# PT08pos.net
KiCad netlist of a schematic drawn in EAGLE
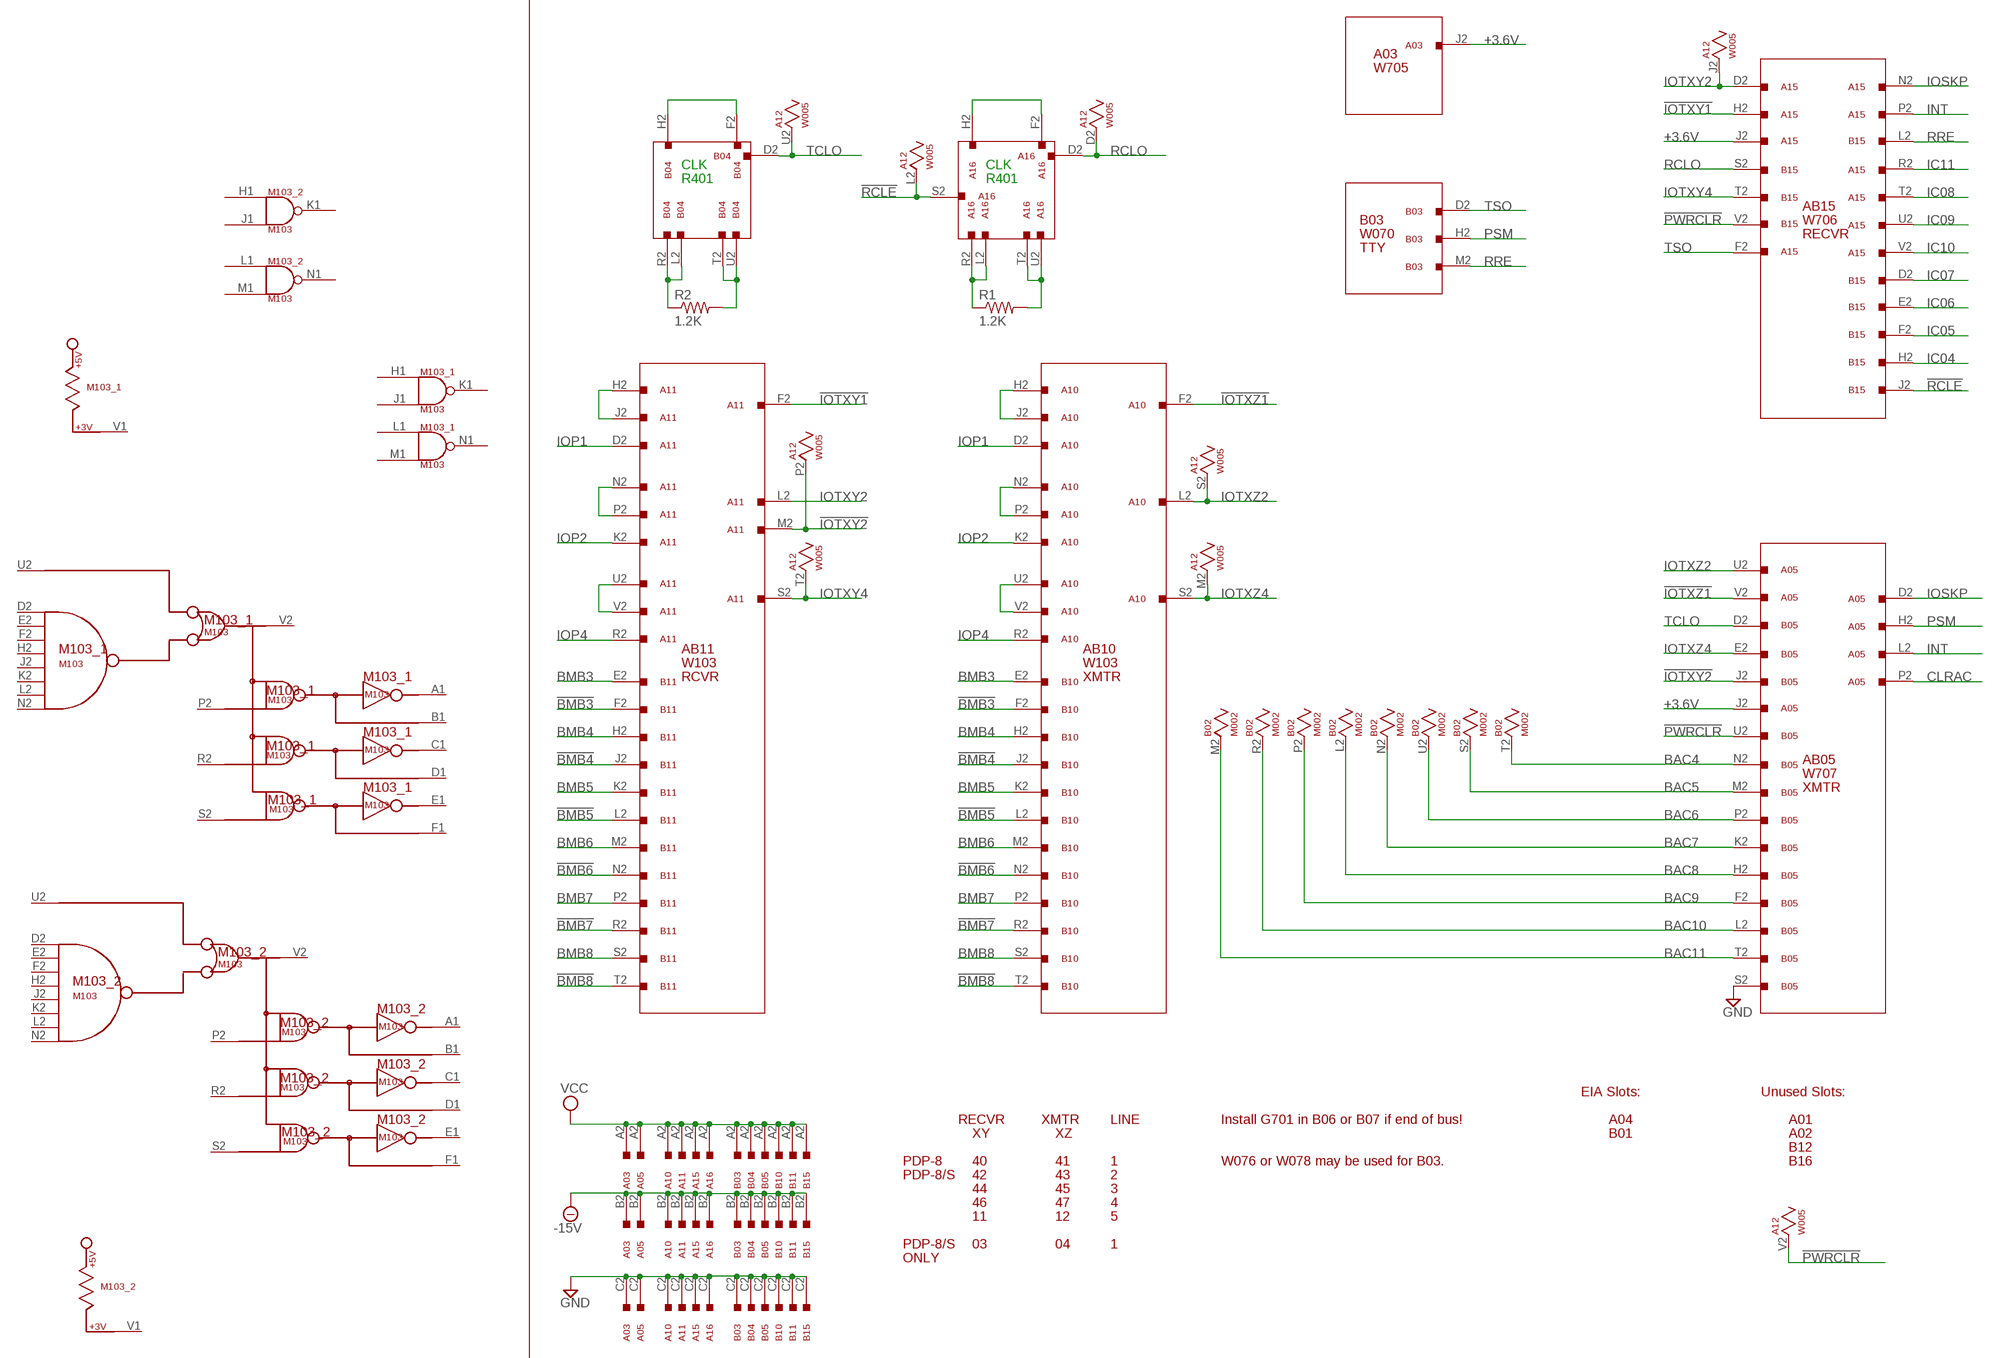
[diagram p0: schematic, sheet 1, part 1 of 2]
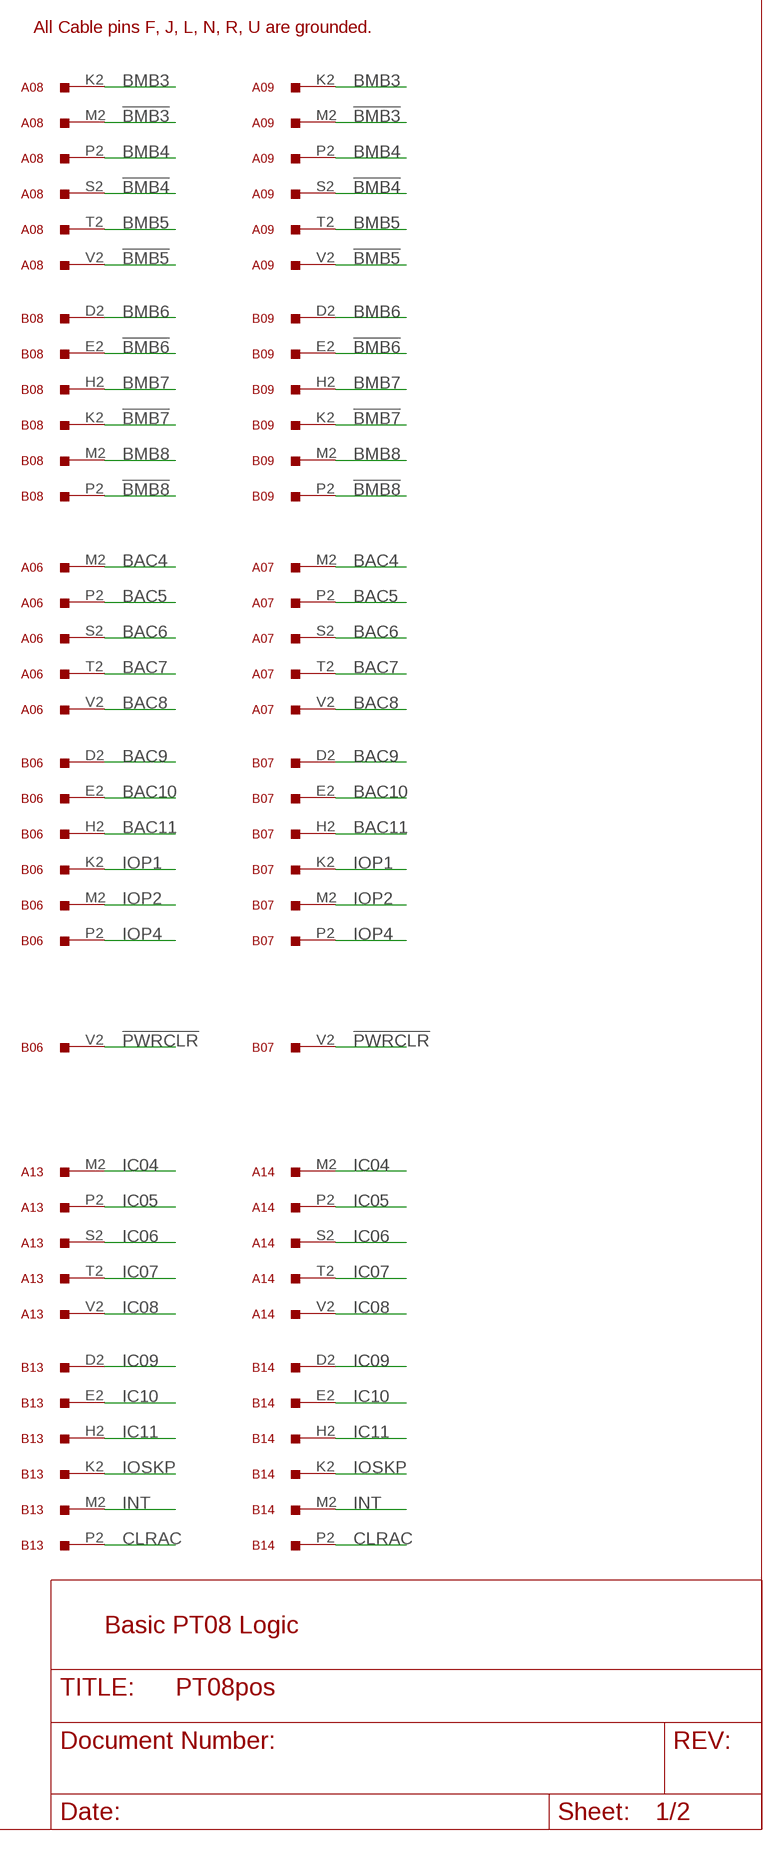
[diagram p1: schematic, sheet 1, part 2 of 2]
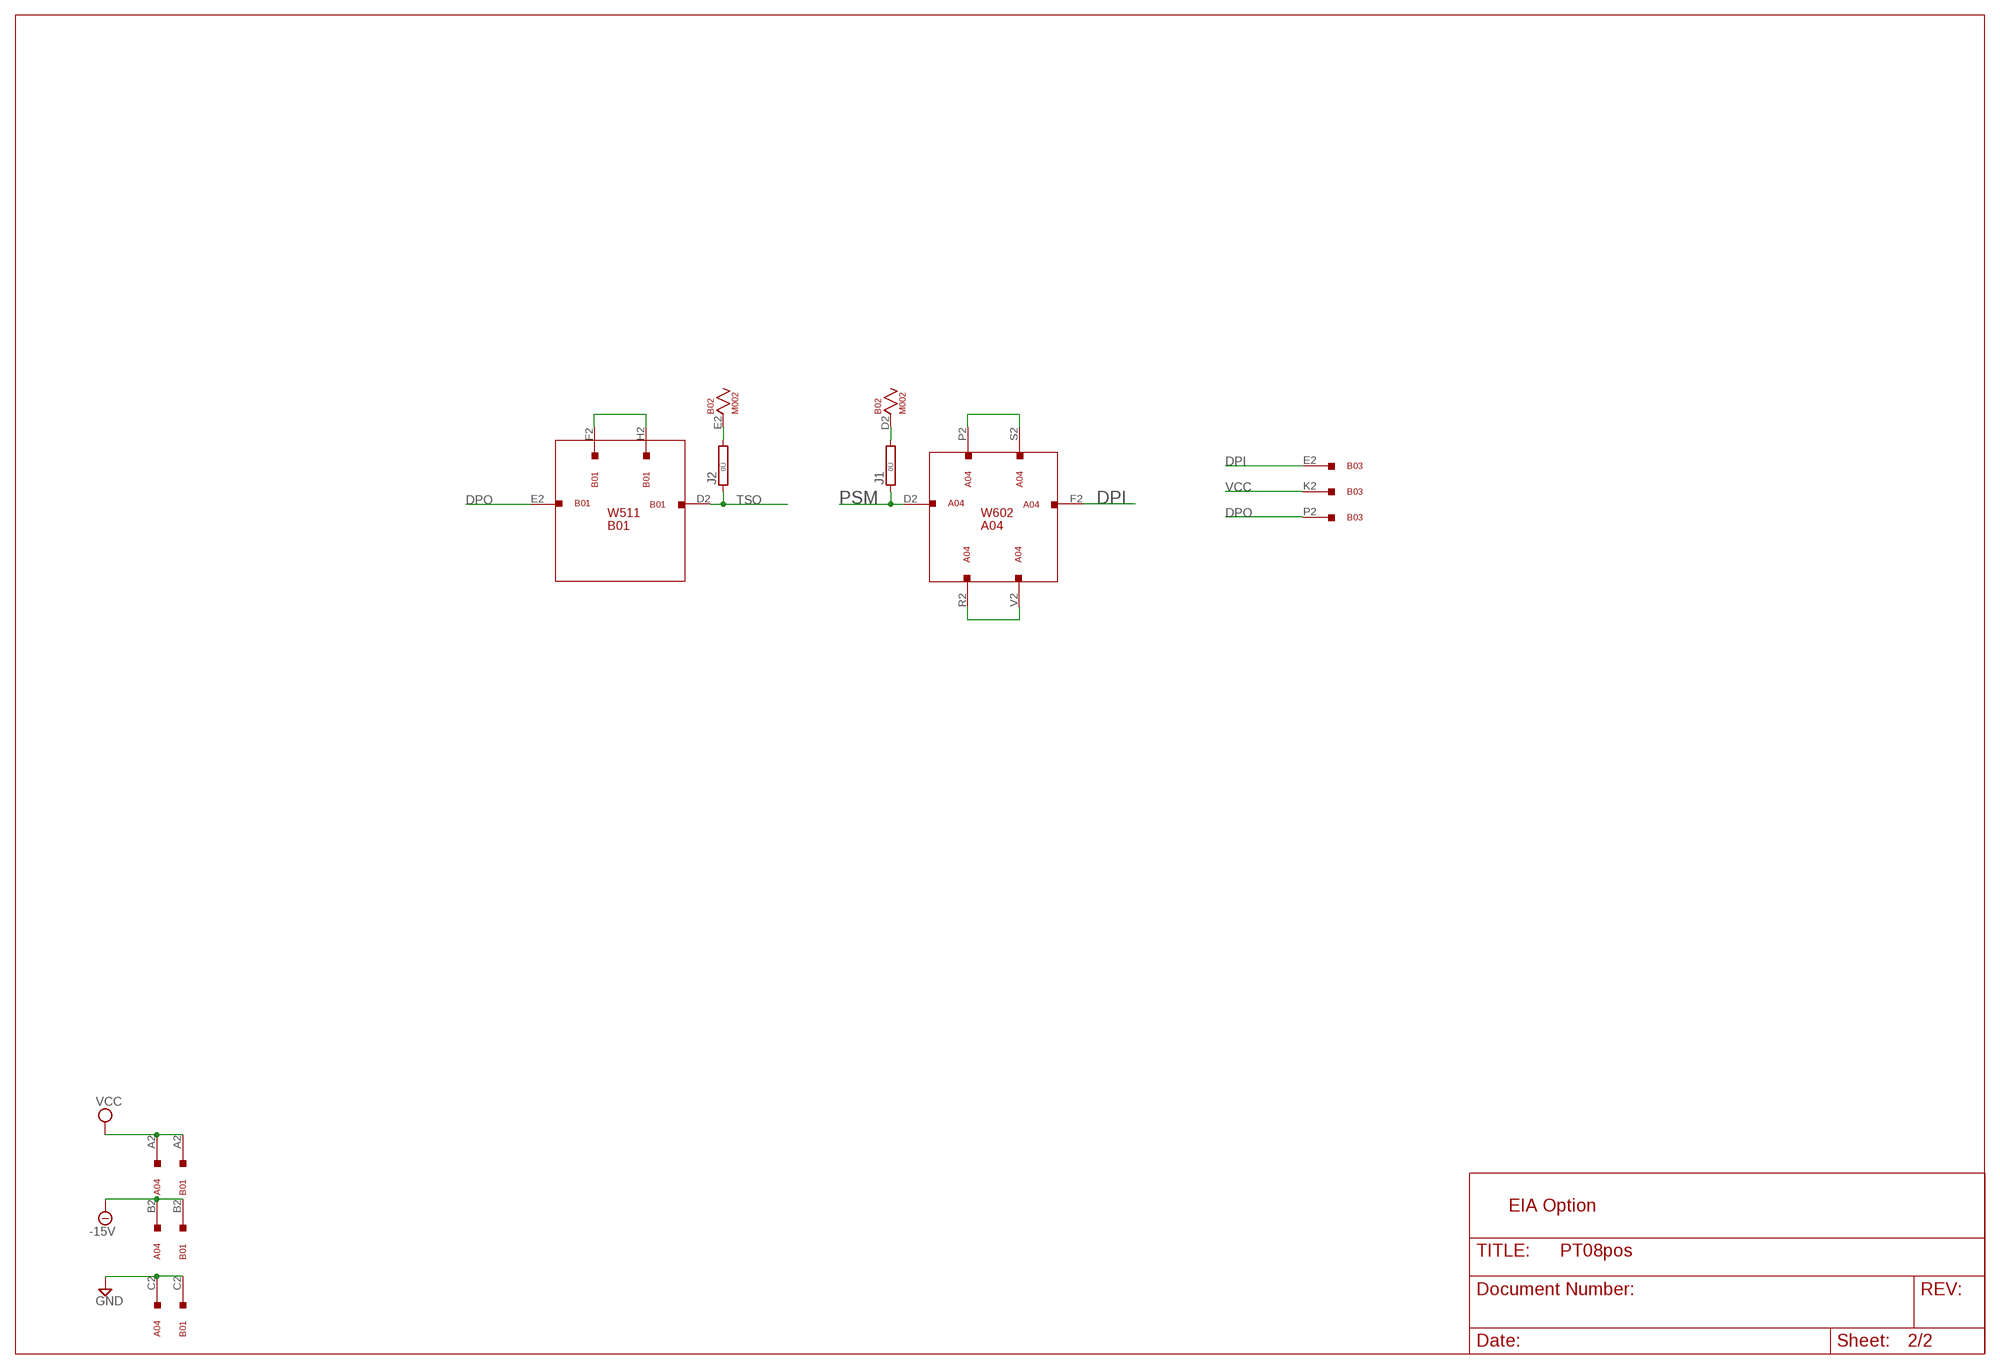
[diagram p2: schematic, sheet 2]

(export (version "E")
  (design (tool "Eeschema 10.0.6"))
  (components
    (comp (ref "A01")
      (value "H807")
      (footprint "eagle-import:H807")
      (libsource (lib "eagle-import") (part "H807"))
    )
    (comp (ref "A02")
      (value "H807")
      (footprint "eagle-import:H807")
      (libsource (lib "eagle-import") (part "H807"))
    )
    (comp (ref "A03")
      (value "W705")
      (footprint "eagle-import:H807")
      (libsource (lib "eagle-import") (part "W023"))
    )
    (comp (ref "A05")
      (value "W707")
      (footprint "eagle-import:H807")
      (libsource (lib "eagle-import") (part "W023"))
    )
    (comp (ref "A06")
      (value "W011")
      (footprint "eagle-import:H807")
      (libsource (lib "eagle-import") (part "W011"))
    )
    (comp (ref "A07")
      (value "W011")
      (footprint "eagle-import:H807")
      (libsource (lib "eagle-import") (part "W011"))
    )
    (comp (ref "A08")
      (value "W011")
      (footprint "eagle-import:H807")
      (libsource (lib "eagle-import") (part "W011"))
    )
    (comp (ref "A09")
      (value "W011")
      (footprint "eagle-import:H807")
      (libsource (lib "eagle-import") (part "W011"))
    )
    (comp (ref "A10")
      (value "W103")
      (footprint "eagle-import:H807")
      (libsource (lib "eagle-import") (part "W023"))
    )
    (comp (ref "A11")
      (value "W103")
      (footprint "eagle-import:H807")
      (libsource (lib "eagle-import") (part "W023"))
    )
    (comp (ref "A12")
      (value "W005")
      (footprint "eagle-import:H807")
      (libsource (lib "eagle-import") (part "W005"))
    )
    (comp (ref "A13")
      (value "W011")
      (footprint "eagle-import:H807")
      (libsource (lib "eagle-import") (part "W011"))
    )
    (comp (ref "A14")
      (value "W011")
      (footprint "eagle-import:H807")
      (libsource (lib "eagle-import") (part "W011"))
    )
    (comp (ref "A15")
      (value "W706")
      (footprint "eagle-import:H807")
      (libsource (lib "eagle-import") (part "W023"))
    )
    (comp (ref "A16")
      (value "R401")
      (footprint "eagle-import:H807")
      (libsource (lib "eagle-import") (part "W023"))
    )
    (comp (ref "B02")
      (value "M002")
      (footprint "eagle-import:H807")
      (libsource (lib "eagle-import") (part "M002"))
    )
    (comp (ref "B03")
      (value "W076")
      (footprint "eagle-import:H807")
      (libsource (lib "eagle-import") (part "W023"))
    )
    (comp (ref "B04")
      (value "R401")
      (footprint "eagle-import:H807")
      (libsource (lib "eagle-import") (part "W023"))
    )
    (comp (ref "B05")
      (value "W707")
      (footprint "eagle-import:H807")
      (libsource (lib "eagle-import") (part "W023"))
    )
    (comp (ref "B06")
      (value "W011")
      (footprint "eagle-import:H807")
      (libsource (lib "eagle-import") (part "W011"))
    )
    (comp (ref "B07")
      (value "W011")
      (footprint "eagle-import:H807")
      (libsource (lib "eagle-import") (part "W011"))
    )
    (comp (ref "B08")
      (value "W011")
      (footprint "eagle-import:H807")
      (libsource (lib "eagle-import") (part "W011"))
    )
    (comp (ref "B09")
      (value "W011")
      (footprint "eagle-import:H807")
      (libsource (lib "eagle-import") (part "W011"))
    )
    (comp (ref "B10")
      (value "W103")
      (footprint "eagle-import:H807")
      (libsource (lib "eagle-import") (part "W023"))
    )
    (comp (ref "B11")
      (value "W103")
      (footprint "eagle-import:H807")
      (libsource (lib "eagle-import") (part "W023"))
    )
    (comp (ref "B12")
      (value "H807")
      (footprint "eagle-import:H807")
      (libsource (lib "eagle-import") (part "H807"))
    )
    (comp (ref "B13")
      (value "W011")
      (footprint "eagle-import:H807")
      (libsource (lib "eagle-import") (part "W011"))
    )
    (comp (ref "B14")
      (value "W011")
      (footprint "eagle-import:H807")
      (libsource (lib "eagle-import") (part "W011"))
    )
    (comp (ref "B15")
      (value "W706")
      (footprint "eagle-import:H807")
      (libsource (lib "eagle-import") (part "W023"))
    )
    (comp (ref "B16")
      (value "H807")
      (footprint "eagle-import:H807")
      (libsource (lib "eagle-import") (part "H807"))
    )
    (comp (ref "M103_1")
      (value "M103")
      (footprint "eagle-import:H807")
      (libsource (lib "eagle-import") (part "M103"))
    )
    (comp (ref "M103_2")
      (value "M103")
      (footprint "eagle-import:H807")
      (libsource (lib "eagle-import") (part "M103"))
    )
    (comp (ref "R1")
      (value "1.2K")
      (footprint "eagle-import:0207_10")
      (libsource (lib "eagle-import") (part "R-US_0207/10"))
    )
    (comp (ref "R2")
      (value "1.2K")
      (footprint "eagle-import:0207_10")
      (libsource (lib "eagle-import") (part "R-US_0207/10"))
    )
    (comp (ref "A04")
      (value "W602")
      (footprint "eagle-import:H807")
      (libsource (lib "eagle-import") (part "W023"))
    )
    (comp (ref "B01")
      (value "W511")
      (footprint "eagle-import:H807")
      (libsource (lib "eagle-import") (part "W023"))
    )
    (comp (ref "J1")
      (value "0R")
      (footprint "eagle-import:0R_10")
      (libsource (lib "eagle-import") (part "0R"))
    )
    (comp (ref "J2")
      (value "0R")
      (footprint "eagle-import:0R_10")
      (libsource (lib "eagle-import") (part "0R"))
    )
  )
  (nets
    (net (code "1") (name "+3.6V") (class "Default")
      (node (ref "A03") (pin "J2") (pinfunction "P$2_J2") (pintype "bidirectional"))
      (node (ref "A05") (pin "J2") (pinfunction "P$2_J2") (pintype "bidirectional"))
      (node (ref "A15") (pin "J2") (pinfunction "P$2_J2") (pintype "bidirectional"))
    )
    (net (code "2") (name "-15V") (class "Default")
      (node (ref "A03") (pin "B2") (pinfunction "P$2_B2") (pintype "bidirectional"))
      (node (ref "A04") (pin "B2") (pinfunction "P$2_B2") (pintype "bidirectional"))
      (node (ref "A05") (pin "B2") (pinfunction "P$2_B2") (pintype "bidirectional"))
      (node (ref "A10") (pin "B2") (pinfunction "P$2_B2") (pintype "bidirectional"))
      (node (ref "A11") (pin "B2") (pinfunction "P$2_B2") (pintype "bidirectional"))
      (node (ref "A15") (pin "B2") (pinfunction "P$2_B2") (pintype "bidirectional"))
      (node (ref "A16") (pin "B2") (pinfunction "P$2_B2") (pintype "bidirectional"))
      (node (ref "B01") (pin "B2") (pinfunction "P$2_B2") (pintype "bidirectional"))
      (node (ref "B03") (pin "B2") (pinfunction "P$2_B2") (pintype "bidirectional"))
      (node (ref "B04") (pin "B2") (pinfunction "P$2_B2") (pintype "bidirectional"))
      (node (ref "B05") (pin "B2") (pinfunction "P$2_B2") (pintype "bidirectional"))
      (node (ref "B10") (pin "B2") (pinfunction "P$2_B2") (pintype "bidirectional"))
      (node (ref "B11") (pin "B2") (pinfunction "P$2_B2") (pintype "bidirectional"))
      (node (ref "B15") (pin "B2") (pinfunction "P$2_B2") (pintype "bidirectional"))
    )
    (net (code "3") (name "BAC4") (class "Default")
      (node (ref "A06") (pin "M2") (pinfunction "P$2_M2") (pintype "bidirectional"))
      (node (ref "A07") (pin "M2") (pinfunction "P$2_M2") (pintype "bidirectional"))
      (node (ref "B02") (pin "T2") (pinfunction "P$1_T2") (pintype "passive"))
      (node (ref "B05") (pin "N2") (pinfunction "P$2_N2") (pintype "bidirectional"))
    )
    (net (code "4") (name "BAC5") (class "Default")
      (node (ref "A06") (pin "P2") (pinfunction "P$2_P2") (pintype "bidirectional"))
      (node (ref "A07") (pin "P2") (pinfunction "P$2_P2") (pintype "bidirectional"))
      (node (ref "B02") (pin "S2") (pinfunction "P$1_S2") (pintype "passive"))
      (node (ref "B05") (pin "M2") (pinfunction "P$2_M2") (pintype "bidirectional"))
    )
    (net (code "5") (name "BAC6") (class "Default")
      (node (ref "A06") (pin "S2") (pinfunction "P$2_S2") (pintype "bidirectional"))
      (node (ref "A07") (pin "S2") (pinfunction "P$2_S2") (pintype "bidirectional"))
      (node (ref "B02") (pin "U2") (pinfunction "P$1_U2") (pintype "passive"))
      (node (ref "B05") (pin "P2") (pinfunction "P$2_P2") (pintype "bidirectional"))
    )
    (net (code "6") (name "BAC7") (class "Default")
      (node (ref "A06") (pin "T2") (pinfunction "P$2_T2") (pintype "bidirectional"))
      (node (ref "A07") (pin "T2") (pinfunction "P$2_T2") (pintype "bidirectional"))
      (node (ref "B02") (pin "N2") (pinfunction "P$1_N2") (pintype "passive"))
      (node (ref "B05") (pin "K2") (pinfunction "P$2_K2") (pintype "bidirectional"))
    )
    (net (code "7") (name "BAC8") (class "Default")
      (node (ref "A06") (pin "V2") (pinfunction "P$2_V2") (pintype "bidirectional"))
      (node (ref "A07") (pin "V2") (pinfunction "P$2_V2") (pintype "bidirectional"))
      (node (ref "B02") (pin "L2") (pinfunction "P$1_L2") (pintype "passive"))
      (node (ref "B05") (pin "H2") (pinfunction "P$2_H2") (pintype "bidirectional"))
    )
    (net (code "8") (name "BAC9") (class "Default")
      (node (ref "B02") (pin "P2") (pinfunction "P$1_P2") (pintype "passive"))
      (node (ref "B05") (pin "F2") (pinfunction "P$2_F2") (pintype "bidirectional"))
      (node (ref "B06") (pin "D2") (pinfunction "P$2_D2") (pintype "bidirectional"))
      (node (ref "B07") (pin "D2") (pinfunction "P$2_D2") (pintype "bidirectional"))
    )
    (net (code "9") (name "BAC10") (class "Default")
      (node (ref "B02") (pin "R2") (pinfunction "P$1_R2") (pintype "passive"))
      (node (ref "B05") (pin "L2") (pinfunction "P$2_L2") (pintype "bidirectional"))
      (node (ref "B06") (pin "E2") (pinfunction "P$2_E2") (pintype "bidirectional"))
      (node (ref "B07") (pin "E2") (pinfunction "P$2_E2") (pintype "bidirectional"))
    )
    (net (code "10") (name "BAC11") (class "Default")
      (node (ref "B02") (pin "M2") (pinfunction "P$1_M2") (pintype "passive"))
      (node (ref "B05") (pin "T2") (pinfunction "P$2_T2") (pintype "bidirectional"))
      (node (ref "B06") (pin "H2") (pinfunction "P$2_H2") (pintype "bidirectional"))
      (node (ref "B07") (pin "H2") (pinfunction "P$2_H2") (pintype "bidirectional"))
    )
    (net (code "11") (name "BMB3") (class "Default")
      (node (ref "A08") (pin "K2") (pinfunction "P$2_K2") (pintype "bidirectional"))
      (node (ref "A09") (pin "K2") (pinfunction "P$2_K2") (pintype "bidirectional"))
      (node (ref "B10") (pin "E2") (pinfunction "P$2_E2") (pintype "bidirectional"))
      (node (ref "B11") (pin "E2") (pinfunction "P$2_E2") (pintype "bidirectional"))
    )
    (net (code "12") (name "BMB4") (class "Default")
      (node (ref "A08") (pin "P2") (pinfunction "P$2_P2") (pintype "bidirectional"))
      (node (ref "A09") (pin "P2") (pinfunction "P$2_P2") (pintype "bidirectional"))
      (node (ref "B10") (pin "H2") (pinfunction "P$2_H2") (pintype "bidirectional"))
      (node (ref "B11") (pin "H2") (pinfunction "P$2_H2") (pintype "bidirectional"))
    )
    (net (code "13") (name "BMB5") (class "Default")
      (node (ref "A08") (pin "T2") (pinfunction "P$2_T2") (pintype "bidirectional"))
      (node (ref "A09") (pin "T2") (pinfunction "P$2_T2") (pintype "bidirectional"))
      (node (ref "B10") (pin "K2") (pinfunction "P$2_K2") (pintype "bidirectional"))
      (node (ref "B11") (pin "K2") (pinfunction "P$2_K2") (pintype "bidirectional"))
    )
    (net (code "14") (name "BMB6") (class "Default")
      (node (ref "B08") (pin "D2") (pinfunction "P$2_D2") (pintype "bidirectional"))
      (node (ref "B09") (pin "D2") (pinfunction "P$2_D2") (pintype "bidirectional"))
      (node (ref "B10") (pin "M2") (pinfunction "P$2_M2") (pintype "bidirectional"))
      (node (ref "B11") (pin "M2") (pinfunction "P$2_M2") (pintype "bidirectional"))
    )
    (net (code "15") (name "BMB7") (class "Default")
      (node (ref "B08") (pin "H2") (pinfunction "P$2_H2") (pintype "bidirectional"))
      (node (ref "B09") (pin "H2") (pinfunction "P$2_H2") (pintype "bidirectional"))
      (node (ref "B10") (pin "P2") (pinfunction "P$2_P2") (pintype "bidirectional"))
      (node (ref "B11") (pin "P2") (pinfunction "P$2_P2") (pintype "bidirectional"))
    )
    (net (code "16") (name "BMB8") (class "Default")
      (node (ref "B08") (pin "M2") (pinfunction "P$2_M2") (pintype "bidirectional"))
      (node (ref "B09") (pin "M2") (pinfunction "P$2_M2") (pintype "bidirectional"))
      (node (ref "B10") (pin "S2") (pinfunction "P$2_S2") (pintype "bidirectional"))
      (node (ref "B11") (pin "S2") (pinfunction "P$2_S2") (pintype "bidirectional"))
    )
    (net (code "17") (name "CLRAC") (class "Default")
      (node (ref "A05") (pin "P2") (pinfunction "P$2_P2") (pintype "bidirectional"))
      (node (ref "B13") (pin "P2") (pinfunction "P$2_P2") (pintype "bidirectional"))
      (node (ref "B14") (pin "P2") (pinfunction "P$2_P2") (pintype "bidirectional"))
    )
    (net (code "18") (name "DPI") (class "Default")
      (node (ref "A04") (pin "F2") (pinfunction "P$2_F2") (pintype "bidirectional"))
      (node (ref "B03") (pin "E2") (pinfunction "P$2_E2") (pintype "bidirectional"))
    )
    (net (code "19") (name "DPO") (class "Default")
      (node (ref "B01") (pin "E2") (pinfunction "P$2_E2") (pintype "bidirectional"))
      (node (ref "B03") (pin "P2") (pinfunction "P$2_P2") (pintype "bidirectional"))
    )
    (net (code "20") (name "GND") (class "Default")
      (node (ref "A03") (pin "C2") (pinfunction "P$2_C2") (pintype "bidirectional"))
      (node (ref "A04") (pin "C2") (pinfunction "P$2_C2") (pintype "bidirectional"))
      (node (ref "A05") (pin "C2") (pinfunction "P$2_C2") (pintype "bidirectional"))
      (node (ref "A10") (pin "C2") (pinfunction "P$2_C2") (pintype "bidirectional"))
      (node (ref "A11") (pin "C2") (pinfunction "P$2_C2") (pintype "bidirectional"))
      (node (ref "A15") (pin "C2") (pinfunction "P$2_C2") (pintype "bidirectional"))
      (node (ref "A16") (pin "C2") (pinfunction "P$2_C2") (pintype "bidirectional"))
      (node (ref "B01") (pin "C2") (pinfunction "P$2_C2") (pintype "bidirectional"))
      (node (ref "B03") (pin "C2") (pinfunction "P$2_C2") (pintype "bidirectional"))
      (node (ref "B04") (pin "C2") (pinfunction "P$2_C2") (pintype "bidirectional"))
      (node (ref "B05") (pin "C2") (pinfunction "P$2_C2") (pintype "bidirectional"))
      (node (ref "B05") (pin "S2") (pinfunction "P$2_S2") (pintype "bidirectional"))
      (node (ref "B10") (pin "C2") (pinfunction "P$2_C2") (pintype "bidirectional"))
      (node (ref "B11") (pin "C2") (pinfunction "P$2_C2") (pintype "bidirectional"))
      (node (ref "B15") (pin "C2") (pinfunction "P$2_C2") (pintype "bidirectional"))
    )
    (net (code "21") (name "IC04") (class "Default")
      (node (ref "A13") (pin "M2") (pinfunction "P$2_M2") (pintype "bidirectional"))
      (node (ref "A14") (pin "M2") (pinfunction "P$2_M2") (pintype "bidirectional"))
      (node (ref "B15") (pin "H2") (pinfunction "P$2_H2") (pintype "bidirectional"))
    )
    (net (code "22") (name "IC05") (class "Default")
      (node (ref "A13") (pin "P2") (pinfunction "P$2_P2") (pintype "bidirectional"))
      (node (ref "A14") (pin "P2") (pinfunction "P$2_P2") (pintype "bidirectional"))
      (node (ref "B15") (pin "F2") (pinfunction "P$2_F2") (pintype "bidirectional"))
    )
    (net (code "23") (name "IC06") (class "Default")
      (node (ref "A13") (pin "S2") (pinfunction "P$2_S2") (pintype "bidirectional"))
      (node (ref "A14") (pin "S2") (pinfunction "P$2_S2") (pintype "bidirectional"))
      (node (ref "B15") (pin "E2") (pinfunction "P$2_E2") (pintype "bidirectional"))
    )
    (net (code "24") (name "IC07") (class "Default")
      (node (ref "A13") (pin "T2") (pinfunction "P$2_T2") (pintype "bidirectional"))
      (node (ref "A14") (pin "T2") (pinfunction "P$2_T2") (pintype "bidirectional"))
      (node (ref "B15") (pin "D2") (pinfunction "P$2_D2") (pintype "bidirectional"))
    )
    (net (code "25") (name "IC08") (class "Default")
      (node (ref "A13") (pin "V2") (pinfunction "P$2_V2") (pintype "bidirectional"))
      (node (ref "A14") (pin "V2") (pinfunction "P$2_V2") (pintype "bidirectional"))
      (node (ref "A15") (pin "T2") (pinfunction "P$2_T2") (pintype "bidirectional"))
    )
    (net (code "26") (name "IC09") (class "Default")
      (node (ref "A15") (pin "U2") (pinfunction "P$2_U2") (pintype "bidirectional"))
      (node (ref "B13") (pin "D2") (pinfunction "P$2_D2") (pintype "bidirectional"))
      (node (ref "B14") (pin "D2") (pinfunction "P$2_D2") (pintype "bidirectional"))
    )
    (net (code "27") (name "IC10") (class "Default")
      (node (ref "A15") (pin "V2") (pinfunction "P$2_V2") (pintype "bidirectional"))
      (node (ref "B13") (pin "E2") (pinfunction "P$2_E2") (pintype "bidirectional"))
      (node (ref "B14") (pin "E2") (pinfunction "P$2_E2") (pintype "bidirectional"))
    )
    (net (code "28") (name "IC11") (class "Default")
      (node (ref "A15") (pin "R2") (pinfunction "P$2_R2") (pintype "bidirectional"))
      (node (ref "B13") (pin "H2") (pinfunction "P$2_H2") (pintype "bidirectional"))
      (node (ref "B14") (pin "H2") (pinfunction "P$2_H2") (pintype "bidirectional"))
    )
    (net (code "29") (name "INT") (class "Default")
      (node (ref "A05") (pin "L2") (pinfunction "P$2_L2") (pintype "bidirectional"))
      (node (ref "A15") (pin "P2") (pinfunction "P$2_P2") (pintype "bidirectional"))
      (node (ref "B13") (pin "M2") (pinfunction "P$2_M2") (pintype "bidirectional"))
      (node (ref "B14") (pin "M2") (pinfunction "P$2_M2") (pintype "bidirectional"))
    )
    (net (code "30") (name "IOP1") (class "Default")
      (node (ref "A10") (pin "D2") (pinfunction "P$2_D2") (pintype "bidirectional"))
      (node (ref "A11") (pin "D2") (pinfunction "P$2_D2") (pintype "bidirectional"))
      (node (ref "B06") (pin "K2") (pinfunction "P$2_K2") (pintype "bidirectional"))
      (node (ref "B07") (pin "K2") (pinfunction "P$2_K2") (pintype "bidirectional"))
    )
    (net (code "31") (name "IOP2") (class "Default")
      (node (ref "A10") (pin "K2") (pinfunction "P$2_K2") (pintype "bidirectional"))
      (node (ref "A11") (pin "K2") (pinfunction "P$2_K2") (pintype "bidirectional"))
      (node (ref "B06") (pin "M2") (pinfunction "P$2_M2") (pintype "bidirectional"))
      (node (ref "B07") (pin "M2") (pinfunction "P$2_M2") (pintype "bidirectional"))
    )
    (net (code "32") (name "IOP4") (class "Default")
      (node (ref "A10") (pin "R2") (pinfunction "P$2_R2") (pintype "bidirectional"))
      (node (ref "A11") (pin "R2") (pinfunction "P$2_R2") (pintype "bidirectional"))
      (node (ref "B06") (pin "P2") (pinfunction "P$2_P2") (pintype "bidirectional"))
      (node (ref "B07") (pin "P2") (pinfunction "P$2_P2") (pintype "bidirectional"))
    )
    (net (code "33") (name "IOSKP") (class "Default")
      (node (ref "A05") (pin "D2") (pinfunction "P$2_D2") (pintype "bidirectional"))
      (node (ref "A15") (pin "N2") (pinfunction "P$2_N2") (pintype "bidirectional"))
      (node (ref "B13") (pin "K2") (pinfunction "P$2_K2") (pintype "bidirectional"))
      (node (ref "B14") (pin "K2") (pinfunction "P$2_K2") (pintype "bidirectional"))
    )
    (net (code "34") (name "IOTXY2") (class "Default")
      (node (ref "A11") (pin "L2") (pinfunction "P$2_L2") (pintype "bidirectional"))
      (node (ref "A12") (pin "J2") (pinfunction "P$1_J2") (pintype "passive"))
      (node (ref "A15") (pin "D2") (pinfunction "P$2_D2") (pintype "bidirectional"))
    )
    (net (code "35") (name "IOTXY4") (class "Default")
      (node (ref "A11") (pin "S2") (pinfunction "P$2_S2") (pintype "bidirectional"))
      (node (ref "A12") (pin "T2") (pinfunction "P$1_T2") (pintype "passive"))
      (node (ref "B15") (pin "T2") (pinfunction "P$2_T2") (pintype "bidirectional"))
    )
    (net (code "36") (name "IOTXZ2") (class "Default")
      (node (ref "A05") (pin "U2") (pinfunction "P$2_U2") (pintype "bidirectional"))
      (node (ref "A10") (pin "L2") (pinfunction "P$2_L2") (pintype "bidirectional"))
      (node (ref "A12") (pin "S2") (pinfunction "P$1_S2") (pintype "passive"))
    )
    (net (code "37") (name "IOTXZ4") (class "Default")
      (node (ref "A10") (pin "S2") (pinfunction "P$2_S2") (pintype "bidirectional"))
      (node (ref "A12") (pin "M2") (pinfunction "P$1_M2") (pintype "passive"))
      (node (ref "B05") (pin "E2") (pinfunction "P$2_E2") (pintype "bidirectional"))
    )
    (net (code "38") (name "Net-(A04M-P$2)") (class "Default")
      (node (ref "A04") (pin "P2") (pinfunction "P$2_P2") (pintype "bidirectional"))
      (node (ref "A04") (pin "S2") (pinfunction "P$2_S2") (pintype "bidirectional"))
    )
    (net (code "39") (name "Net-(A04N-P$2)") (class "Default")
      (node (ref "A04") (pin "R2") (pinfunction "P$2_R2") (pintype "bidirectional"))
      (node (ref "A04") (pin "V2") (pinfunction "P$2_V2") (pintype "bidirectional"))
    )
    (net (code "40") (name "Net-(A10G-P$2)") (class "Default")
      (node (ref "A10") (pin "H2") (pinfunction "P$2_H2") (pintype "bidirectional"))
      (node (ref "A10") (pin "J2") (pinfunction "P$2_J2") (pintype "bidirectional"))
    )
    (net (code "41") (name "Net-(A10L-P$2)") (class "Default")
      (node (ref "A10") (pin "N2") (pinfunction "P$2_N2") (pintype "bidirectional"))
      (node (ref "A10") (pin "P2") (pinfunction "P$2_P2") (pintype "bidirectional"))
    )
    (net (code "42") (name "Net-(A10Q-P$2)") (class "Default")
      (node (ref "A10") (pin "U2") (pinfunction "P$2_U2") (pintype "bidirectional"))
      (node (ref "A10") (pin "V2") (pinfunction "P$2_V2") (pintype "bidirectional"))
    )
    (net (code "43") (name "Net-(A11G-P$2)") (class "Default")
      (node (ref "A11") (pin "H2") (pinfunction "P$2_H2") (pintype "bidirectional"))
      (node (ref "A11") (pin "J2") (pinfunction "P$2_J2") (pintype "bidirectional"))
    )
    (net (code "44") (name "Net-(A11L-P$2)") (class "Default")
      (node (ref "A11") (pin "N2") (pinfunction "P$2_N2") (pintype "bidirectional"))
      (node (ref "A11") (pin "P2") (pinfunction "P$2_P2") (pintype "bidirectional"))
    )
    (net (code "45") (name "Net-(A11Q-P$2)") (class "Default")
      (node (ref "A11") (pin "U2") (pinfunction "P$2_U2") (pintype "bidirectional"))
      (node (ref "A11") (pin "V2") (pinfunction "P$2_V2") (pintype "bidirectional"))
    )
    (net (code "46") (name "Net-(A16F-P$2)") (class "Default")
      (node (ref "A16") (pin "F2") (pinfunction "P$2_F2") (pintype "bidirectional"))
      (node (ref "A16") (pin "H2") (pinfunction "P$2_H2") (pintype "bidirectional"))
    )
    (net (code "47") (name "Net-(A16J-P$2)") (class "Default")
      (node (ref "A16") (pin "L2") (pinfunction "P$2_L2") (pintype "bidirectional"))
      (node (ref "A16") (pin "R2") (pinfunction "P$2_R2") (pintype "bidirectional"))
      (node (ref "R1") (pin "1") (pinfunction "1_1") (pintype "passive"))
    )
    (net (code "48") (name "Net-(A16P-P$2)") (class "Default")
      (node (ref "A16") (pin "T2") (pinfunction "P$2_T2") (pintype "bidirectional"))
      (node (ref "A16") (pin "U2") (pinfunction "P$2_U2") (pintype "bidirectional"))
      (node (ref "R1") (pin "2") (pinfunction "2_2") (pintype "passive"))
    )
    (net (code "49") (name "Net-(B01F-P$2)") (class "Default")
      (node (ref "B01") (pin "F2") (pinfunction "P$2_F2") (pintype "bidirectional"))
      (node (ref "B01") (pin "H2") (pinfunction "P$2_H2") (pintype "bidirectional"))
    )
    (net (code "50") (name "Net-(B02A-P$1)") (class "Default")
      (node (ref "B02") (pin "D2") (pinfunction "P$1_D2") (pintype "passive"))
      (node (ref "J1") (pin "2") (pinfunction "2_2") (pintype "passive"))
    )
    (net (code "51") (name "Net-(B02B-P$1)") (class "Default")
      (node (ref "B02") (pin "E2") (pinfunction "P$1_E2") (pintype "passive"))
      (node (ref "J2") (pin "2") (pinfunction "2_2") (pintype "passive"))
    )
    (net (code "52") (name "Net-(B04F-P$2)") (class "Default")
      (node (ref "B04") (pin "F2") (pinfunction "P$2_F2") (pintype "bidirectional"))
      (node (ref "B04") (pin "H2") (pinfunction "P$2_H2") (pintype "bidirectional"))
    )
    (net (code "53") (name "Net-(B04J-P$2)") (class "Default")
      (node (ref "B04") (pin "L2") (pinfunction "P$2_L2") (pintype "bidirectional"))
      (node (ref "B04") (pin "R2") (pinfunction "P$2_R2") (pintype "bidirectional"))
      (node (ref "R2") (pin "1") (pinfunction "1_1") (pintype "passive"))
    )
    (net (code "54") (name "Net-(B04P-P$2)") (class "Default")
      (node (ref "B04") (pin "T2") (pinfunction "P$2_T2") (pintype "bidirectional"))
      (node (ref "B04") (pin "U2") (pinfunction "P$2_U2") (pintype "bidirectional"))
      (node (ref "R2") (pin "2") (pinfunction "2_2") (pintype "passive"))
    )
    (net (code "55") (name "PSM") (class "Default")
      (node (ref "A04") (pin "D2") (pinfunction "P$2_D2") (pintype "bidirectional"))
      (node (ref "A05") (pin "H2") (pinfunction "P$2_H2") (pintype "bidirectional"))
      (node (ref "B03") (pin "H2") (pinfunction "P$2_H2") (pintype "bidirectional"))
      (node (ref "J1") (pin "1") (pinfunction "1_1") (pintype "passive"))
    )
    (net (code "56") (name "RCLO") (class "Default")
      (node (ref "A12") (pin "D2") (pinfunction "P$1_D2") (pintype "passive"))
      (node (ref "A16") (pin "D2") (pinfunction "P$2_D2") (pintype "bidirectional"))
      (node (ref "B15") (pin "S2") (pinfunction "P$2_S2") (pintype "bidirectional"))
    )
    (net (code "57") (name "RRE") (class "Default")
      (node (ref "B03") (pin "M2") (pinfunction "P$2_M2") (pintype "bidirectional"))
      (node (ref "B15") (pin "L2") (pinfunction "P$2_L2") (pintype "bidirectional"))
    )
    (net (code "58") (name "TCLO") (class "Default")
      (node (ref "A12") (pin "U2") (pinfunction "P$1_U2") (pintype "passive"))
      (node (ref "B04") (pin "D2") (pinfunction "P$2_D2") (pintype "bidirectional"))
      (node (ref "B05") (pin "D2") (pinfunction "P$2_D2") (pintype "bidirectional"))
    )
    (net (code "59") (name "TSO") (class "Default")
      (node (ref "A15") (pin "F2") (pinfunction "P$2_F2") (pintype "bidirectional"))
      (node (ref "B01") (pin "D2") (pinfunction "P$2_D2") (pintype "bidirectional"))
      (node (ref "B03") (pin "D2") (pinfunction "P$2_D2") (pintype "bidirectional"))
      (node (ref "J2") (pin "1") (pinfunction "1_1") (pintype "passive"))
    )
    (net (code "60") (name "VCC") (class "Default")
      (node (ref "A03") (pin "A2") (pinfunction "P$2_A2") (pintype "bidirectional"))
      (node (ref "A04") (pin "A2") (pinfunction "P$2_A2") (pintype "bidirectional"))
      (node (ref "A05") (pin "A2") (pinfunction "P$2_A2") (pintype "bidirectional"))
      (node (ref "A10") (pin "A2") (pinfunction "P$2_A2") (pintype "bidirectional"))
      (node (ref "A11") (pin "A2") (pinfunction "P$2_A2") (pintype "bidirectional"))
      (node (ref "A15") (pin "A2") (pinfunction "P$2_A2") (pintype "bidirectional"))
      (node (ref "A16") (pin "A2") (pinfunction "P$2_A2") (pintype "bidirectional"))
      (node (ref "B01") (pin "A2") (pinfunction "P$2_A2") (pintype "bidirectional"))
      (node (ref "B03") (pin "A2") (pinfunction "P$2_A2") (pintype "bidirectional"))
      (node (ref "B03") (pin "K2") (pinfunction "P$2_K2") (pintype "bidirectional"))
      (node (ref "B04") (pin "A2") (pinfunction "P$2_A2") (pintype "bidirectional"))
      (node (ref "B05") (pin "A2") (pinfunction "P$2_A2") (pintype "bidirectional"))
      (node (ref "B10") (pin "A2") (pinfunction "P$2_A2") (pintype "bidirectional"))
      (node (ref "B11") (pin "A2") (pinfunction "P$2_A2") (pintype "bidirectional"))
      (node (ref "B15") (pin "A2") (pinfunction "P$2_A2") (pintype "bidirectional"))
    )
    (net (code "61") (name "unconnected-(M103_1-PadA1)") (class "Default")
      (node (ref "M103_1") (pin "A1") (pinfunction "A1_A1") (pintype "output"))
    )
    (net (code "62") (name "unconnected-(M103_1-PadB1)") (class "Default")
      (node (ref "M103_1") (pin "B1") (pinfunction "B1_B1") (pintype "output"))
    )
    (net (code "63") (name "unconnected-(M103_1-PadC1)") (class "Default")
      (node (ref "M103_1") (pin "C1") (pinfunction "C1_C1") (pintype "output"))
    )
    (net (code "64") (name "unconnected-(M103_1-PadD1)") (class "Default")
      (node (ref "M103_1") (pin "D1") (pinfunction "D1_D1") (pintype "output"))
    )
    (net (code "65") (name "unconnected-(M103_1-PadD2)") (class "Default")
      (node (ref "M103_1") (pin "D2") (pinfunction "D2_D2") (pintype "input"))
    )
    (net (code "66") (name "unconnected-(M103_1-PadE1)") (class "Default")
      (node (ref "M103_1") (pin "E1") (pinfunction "E1_E1") (pintype "output"))
    )
    (net (code "67") (name "unconnected-(M103_1-PadE2)") (class "Default")
      (node (ref "M103_1") (pin "E2") (pinfunction "E2_E2") (pintype "input"))
    )
    (net (code "68") (name "unconnected-(M103_1-PadF1)") (class "Default")
      (node (ref "M103_1") (pin "F1") (pinfunction "F1_F1") (pintype "output"))
    )
    (net (code "69") (name "unconnected-(M103_1-PadF2)") (class "Default")
      (node (ref "M103_1") (pin "F2") (pinfunction "F2_F2") (pintype "input"))
    )
    (net (code "70") (name "unconnected-(M103_1-PadH2)") (class "Default")
      (node (ref "M103_1") (pin "H2") (pinfunction "H2_H2") (pintype "input"))
    )
    (net (code "71") (name "unconnected-(M103_1-PadJ2)") (class "Default")
      (node (ref "M103_1") (pin "J2") (pinfunction "J2_J2") (pintype "input"))
    )
    (net (code "72") (name "unconnected-(M103_1-PadK2)") (class "Default")
      (node (ref "M103_1") (pin "K2") (pinfunction "K2_K2") (pintype "input"))
    )
    (net (code "73") (name "unconnected-(M103_1-PadL2)") (class "Default")
      (node (ref "M103_1") (pin "L2") (pinfunction "L2_L2") (pintype "input"))
    )
    (net (code "74") (name "unconnected-(M103_1-PadN2)") (class "Default")
      (node (ref "M103_1") (pin "N2") (pinfunction "N2_N2") (pintype "input"))
    )
    (net (code "75") (name "unconnected-(M103_1-PadP2)") (class "Default")
      (node (ref "M103_1") (pin "P2") (pinfunction "P2_P2") (pintype "input"))
    )
    (net (code "76") (name "unconnected-(M103_1-PadR2)") (class "Default")
      (node (ref "M103_1") (pin "R2") (pinfunction "R2_R2") (pintype "input"))
    )
    (net (code "77") (name "unconnected-(M103_1-PadS2)") (class "Default")
      (node (ref "M103_1") (pin "S2") (pinfunction "S2_S2") (pintype "input"))
    )
    (net (code "78") (name "unconnected-(M103_1-PadU2)") (class "Default")
      (node (ref "M103_1") (pin "U2") (pinfunction "U2_U2") (pintype "input"))
    )
    (net (code "79") (name "unconnected-(M103_1-PadV2)") (class "Default")
      (node (ref "M103_1") (pin "V2") (pinfunction "V2_V2") (pintype "output"))
    )
    (net (code "80") (name "unconnected-(M103_1C-IN1-PadH1)") (class "Default")
      (node (ref "M103_1") (pin "H1") (pinfunction "IN1_H1") (pintype "input"))
    )
    (net (code "81") (name "unconnected-(M103_1C-IN2-PadJ1)") (class "Default")
      (node (ref "M103_1") (pin "J1") (pinfunction "IN2_J1") (pintype "input"))
    )
    (net (code "82") (name "unconnected-(M103_1C-OUT-PadK1)") (class "Default")
      (node (ref "M103_1") (pin "K1") (pinfunction "OUT_K1") (pintype "output"))
    )
    (net (code "83") (name "unconnected-(M103_1D-IN1-PadL1)") (class "Default")
      (node (ref "M103_1") (pin "L1") (pinfunction "IN1_L1") (pintype "input"))
    )
    (net (code "84") (name "unconnected-(M103_1D-IN2-PadM1)") (class "Default")
      (node (ref "M103_1") (pin "M1") (pinfunction "IN2_M1") (pintype "input"))
    )
    (net (code "85") (name "unconnected-(M103_1D-OUT-PadN1)") (class "Default")
      (node (ref "M103_1") (pin "N1") (pinfunction "OUT_N1") (pintype "output"))
    )
    (net (code "86") (name "unconnected-(M103_1E-P$1-PadV1)") (class "Default")
      (node (ref "M103_1") (pin "V1") (pinfunction "P$1_V1") (pintype "passive"))
    )
    (net (code "87") (name "unconnected-(M103_2-PadA1)") (class "Default")
      (node (ref "M103_2") (pin "A1") (pinfunction "A1_A1") (pintype "output"))
    )
    (net (code "88") (name "unconnected-(M103_2-PadB1)") (class "Default")
      (node (ref "M103_2") (pin "B1") (pinfunction "B1_B1") (pintype "output"))
    )
    (net (code "89") (name "unconnected-(M103_2-PadC1)") (class "Default")
      (node (ref "M103_2") (pin "C1") (pinfunction "C1_C1") (pintype "output"))
    )
    (net (code "90") (name "unconnected-(M103_2-PadD1)") (class "Default")
      (node (ref "M103_2") (pin "D1") (pinfunction "D1_D1") (pintype "output"))
    )
    (net (code "91") (name "unconnected-(M103_2-PadD2)") (class "Default")
      (node (ref "M103_2") (pin "D2") (pinfunction "D2_D2") (pintype "input"))
    )
    (net (code "92") (name "unconnected-(M103_2-PadE1)") (class "Default")
      (node (ref "M103_2") (pin "E1") (pinfunction "E1_E1") (pintype "output"))
    )
    (net (code "93") (name "unconnected-(M103_2-PadE2)") (class "Default")
      (node (ref "M103_2") (pin "E2") (pinfunction "E2_E2") (pintype "input"))
    )
    (net (code "94") (name "unconnected-(M103_2-PadF1)") (class "Default")
      (node (ref "M103_2") (pin "F1") (pinfunction "F1_F1") (pintype "output"))
    )
    (net (code "95") (name "unconnected-(M103_2-PadF2)") (class "Default")
      (node (ref "M103_2") (pin "F2") (pinfunction "F2_F2") (pintype "input"))
    )
    (net (code "96") (name "unconnected-(M103_2-PadH2)") (class "Default")
      (node (ref "M103_2") (pin "H2") (pinfunction "H2_H2") (pintype "input"))
    )
    (net (code "97") (name "unconnected-(M103_2-PadJ2)") (class "Default")
      (node (ref "M103_2") (pin "J2") (pinfunction "J2_J2") (pintype "input"))
    )
    (net (code "98") (name "unconnected-(M103_2-PadK2)") (class "Default")
      (node (ref "M103_2") (pin "K2") (pinfunction "K2_K2") (pintype "input"))
    )
    (net (code "99") (name "unconnected-(M103_2-PadL2)") (class "Default")
      (node (ref "M103_2") (pin "L2") (pinfunction "L2_L2") (pintype "input"))
    )
    (net (code "100") (name "unconnected-(M103_2-PadN2)") (class "Default")
      (node (ref "M103_2") (pin "N2") (pinfunction "N2_N2") (pintype "input"))
    )
    (net (code "101") (name "unconnected-(M103_2-PadP2)") (class "Default")
      (node (ref "M103_2") (pin "P2") (pinfunction "P2_P2") (pintype "input"))
    )
    (net (code "102") (name "unconnected-(M103_2-PadR2)") (class "Default")
      (node (ref "M103_2") (pin "R2") (pinfunction "R2_R2") (pintype "input"))
    )
    (net (code "103") (name "unconnected-(M103_2-PadS2)") (class "Default")
      (node (ref "M103_2") (pin "S2") (pinfunction "S2_S2") (pintype "input"))
    )
    (net (code "104") (name "unconnected-(M103_2-PadU2)") (class "Default")
      (node (ref "M103_2") (pin "U2") (pinfunction "U2_U2") (pintype "input"))
    )
    (net (code "105") (name "unconnected-(M103_2-PadV2)") (class "Default")
      (node (ref "M103_2") (pin "V2") (pinfunction "V2_V2") (pintype "output"))
    )
    (net (code "106") (name "unconnected-(M103_2C-IN1-PadH1)") (class "Default")
      (node (ref "M103_2") (pin "H1") (pinfunction "IN1_H1") (pintype "input"))
    )
    (net (code "107") (name "unconnected-(M103_2C-IN2-PadJ1)") (class "Default")
      (node (ref "M103_2") (pin "J1") (pinfunction "IN2_J1") (pintype "input"))
    )
    (net (code "108") (name "unconnected-(M103_2C-OUT-PadK1)") (class "Default")
      (node (ref "M103_2") (pin "K1") (pinfunction "OUT_K1") (pintype "output"))
    )
    (net (code "109") (name "unconnected-(M103_2D-IN1-PadL1)") (class "Default")
      (node (ref "M103_2") (pin "L1") (pinfunction "IN1_L1") (pintype "input"))
    )
    (net (code "110") (name "unconnected-(M103_2D-IN2-PadM1)") (class "Default")
      (node (ref "M103_2") (pin "M1") (pinfunction "IN2_M1") (pintype "input"))
    )
    (net (code "111") (name "unconnected-(M103_2D-OUT-PadN1)") (class "Default")
      (node (ref "M103_2") (pin "N1") (pinfunction "OUT_N1") (pintype "output"))
    )
    (net (code "112") (name "unconnected-(M103_2E-P$1-PadV1)") (class "Default")
      (node (ref "M103_2") (pin "V1") (pinfunction "P$1_V1") (pintype "passive"))
    )
    (net (code "113") (name "~{BMB3}") (class "Default")
      (node (ref "A08") (pin "M2") (pinfunction "P$2_M2") (pintype "bidirectional"))
      (node (ref "A09") (pin "M2") (pinfunction "P$2_M2") (pintype "bidirectional"))
      (node (ref "B10") (pin "F2") (pinfunction "P$2_F2") (pintype "bidirectional"))
      (node (ref "B11") (pin "F2") (pinfunction "P$2_F2") (pintype "bidirectional"))
    )
    (net (code "114") (name "~{BMB4}") (class "Default")
      (node (ref "A08") (pin "S2") (pinfunction "P$2_S2") (pintype "bidirectional"))
      (node (ref "A09") (pin "S2") (pinfunction "P$2_S2") (pintype "bidirectional"))
      (node (ref "B10") (pin "J2") (pinfunction "P$2_J2") (pintype "bidirectional"))
      (node (ref "B11") (pin "J2") (pinfunction "P$2_J2") (pintype "bidirectional"))
    )
    (net (code "115") (name "~{BMB5}") (class "Default")
      (node (ref "A08") (pin "V2") (pinfunction "P$2_V2") (pintype "bidirectional"))
      (node (ref "A09") (pin "V2") (pinfunction "P$2_V2") (pintype "bidirectional"))
      (node (ref "B10") (pin "L2") (pinfunction "P$2_L2") (pintype "bidirectional"))
      (node (ref "B11") (pin "L2") (pinfunction "P$2_L2") (pintype "bidirectional"))
    )
    (net (code "116") (name "~{BMB6}") (class "Default")
      (node (ref "B08") (pin "E2") (pinfunction "P$2_E2") (pintype "bidirectional"))
      (node (ref "B09") (pin "E2") (pinfunction "P$2_E2") (pintype "bidirectional"))
      (node (ref "B10") (pin "N2") (pinfunction "P$2_N2") (pintype "bidirectional"))
      (node (ref "B11") (pin "N2") (pinfunction "P$2_N2") (pintype "bidirectional"))
    )
    (net (code "117") (name "~{BMB7}") (class "Default")
      (node (ref "B08") (pin "K2") (pinfunction "P$2_K2") (pintype "bidirectional"))
      (node (ref "B09") (pin "K2") (pinfunction "P$2_K2") (pintype "bidirectional"))
      (node (ref "B10") (pin "R2") (pinfunction "P$2_R2") (pintype "bidirectional"))
      (node (ref "B11") (pin "R2") (pinfunction "P$2_R2") (pintype "bidirectional"))
    )
    (net (code "118") (name "~{BMB8}") (class "Default")
      (node (ref "B08") (pin "P2") (pinfunction "P$2_P2") (pintype "bidirectional"))
      (node (ref "B09") (pin "P2") (pinfunction "P$2_P2") (pintype "bidirectional"))
      (node (ref "B10") (pin "T2") (pinfunction "P$2_T2") (pintype "bidirectional"))
      (node (ref "B11") (pin "T2") (pinfunction "P$2_T2") (pintype "bidirectional"))
    )
    (net (code "119") (name "~{IOTXY1}") (class "Default")
      (node (ref "A11") (pin "F2") (pinfunction "P$2_F2") (pintype "bidirectional"))
      (node (ref "A15") (pin "H2") (pinfunction "P$2_H2") (pintype "bidirectional"))
    )
    (net (code "120") (name "~{IOTXY2}") (class "Default")
      (node (ref "A11") (pin "M2") (pinfunction "P$2_M2") (pintype "bidirectional"))
      (node (ref "A12") (pin "P2") (pinfunction "P$1_P2") (pintype "passive"))
      (node (ref "B05") (pin "J2") (pinfunction "P$2_J2") (pintype "bidirectional"))
    )
    (net (code "121") (name "~{IOTXZ1}") (class "Default")
      (node (ref "A05") (pin "V2") (pinfunction "P$2_V2") (pintype "bidirectional"))
      (node (ref "A10") (pin "F2") (pinfunction "P$2_F2") (pintype "bidirectional"))
    )
    (net (code "122") (name "~{PWRCLR}") (class "Default")
      (node (ref "A12") (pin "V2") (pinfunction "P$1_V2") (pintype "passive"))
      (node (ref "B05") (pin "U2") (pinfunction "P$2_U2") (pintype "bidirectional"))
      (node (ref "B06") (pin "V2") (pinfunction "P$2_V2") (pintype "bidirectional"))
      (node (ref "B07") (pin "V2") (pinfunction "P$2_V2") (pintype "bidirectional"))
      (node (ref "B15") (pin "V2") (pinfunction "P$2_V2") (pintype "bidirectional"))
    )
    (net (code "123") (name "~{RCLE}") (class "Default")
      (node (ref "A12") (pin "L2") (pinfunction "P$1_L2") (pintype "passive"))
      (node (ref "A16") (pin "S2") (pinfunction "P$2_S2") (pintype "bidirectional"))
      (node (ref "B15") (pin "J2") (pinfunction "P$2_J2") (pintype "bidirectional"))
    )
  )
)
